# schematic.net
KiCad netlist of a schematic drawn in Altium Designer
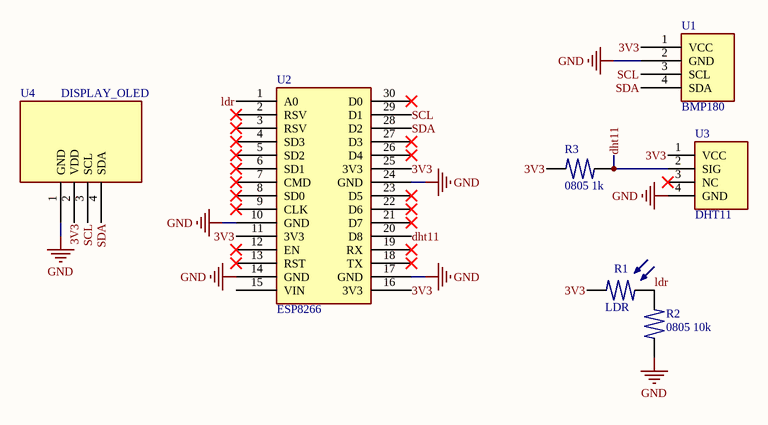
[diagram p0: schematic.SchDoc]

(export (version "E")
  (design (tool "Eeschema 10.0.6"))
  (components
    (comp (ref "R1")
      (value "LDR")
      (footprint "LDR")
      (description "LIGHT DEPENDEND RESISTOR/PHOTORESITOR")
      (libsource (lib "Sensors") (part "LDR"))
    )
    (comp (ref "R2")
      (value "0805 10k")
      (footprint "RESISTOR_0805")
      (libsource (lib "Resistors") (part "RESISTOR_0805"))
    )
    (comp (ref "R3")
      (value "0805 1k")
      (footprint "RESISTOR_0805")
      (libsource (lib "Resistors") (part "RESISTOR_0805"))
    )
    (comp (ref "U1")
      (value "BMP180")
      (footprint "BMP180")
      (description "SENSOR ATMOSPHERIC PRESSURE/TEMPERATURE")
      (libsource (lib "Sensors") (part "BMP180"))
    )
    (comp (ref "U2")
      (value "ESP8266")
      (footprint "ESP8266")
      (description "Microcontoller Board 30 Pins Wifi 2.4GHz BLE 4.2 ESP-12F")
      (libsource (lib "Espressif Microcontrollers") (part "ESP8266"))
    )
    (comp (ref "U3")
      (value "DHT11")
      (footprint "DHT11")
      (description "SENSOR HUMIDITY/TEMPERATURE")
      (libsource (lib "Sensors") (part "DHT11"))
    )
    (comp (ref "U4")
      (value "DISPLAY_OLED")
      (footprint "DISPLAY_OLED")
      (libsource (lib "Displays") (part "DISPLAY_OLED"))
    )
  )
  (nets
    (net (code "1") (name "/3V3") (class "Default")
      (node (ref "R1") (pin "1") (pinfunction "1_1") (pintype "passive"))
      (node (ref "R3") (pin "1") (pinfunction "1_1") (pintype "passive"))
      (node (ref "U1") (pin "1") (pinfunction "VCC_1") (pintype "passive"))
      (node (ref "U2") (pin "11") (pinfunction "3V3_11") (pintype "passive"))
      (node (ref "U2") (pin "16") (pinfunction "3V3_16") (pintype "passive"))
      (node (ref "U2") (pin "25") (pinfunction "3V3_25") (pintype "passive"))
      (node (ref "U3") (pin "1") (pinfunction "VCC_1") (pintype "passive"))
      (node (ref "U4") (pin "2") (pinfunction "VDD_2") (pintype "tri_state"))
    )
    (net (code "2") (name "/SCL") (class "Default")
      (node (ref "U1") (pin "3") (pinfunction "SCL_3") (pintype "passive"))
      (node (ref "U2") (pin "29") (pinfunction "D1_29") (pintype "passive"))
      (node (ref "U4") (pin "3") (pinfunction "SCL_3") (pintype "tri_state"))
    )
    (net (code "3") (name "/SDA") (class "Default")
      (node (ref "U1") (pin "4") (pinfunction "SDA_4") (pintype "passive"))
      (node (ref "U2") (pin "28") (pinfunction "D2_28") (pintype "passive"))
      (node (ref "U4") (pin "4") (pinfunction "SDA_4") (pintype "tri_state"))
    )
    (net (code "4") (name "/dht11") (class "Default")
      (node (ref "R3") (pin "2") (pinfunction "2_2") (pintype "passive"))
      (node (ref "U2") (pin "20") (pinfunction "D8_20") (pintype "passive"))
      (node (ref "U3") (pin "2") (pinfunction "SIG_2") (pintype "passive"))
    )
    (net (code "5") (name "/ldr") (class "Default")
      (node (ref "R1") (pin "2") (pinfunction "2_2") (pintype "passive"))
      (node (ref "R2") (pin "2") (pinfunction "2_2") (pintype "passive"))
      (node (ref "U2") (pin "1") (pinfunction "A0_1") (pintype "passive"))
    )
    (net (code "6") (name "GND") (class "Default")
      (node (ref "R2") (pin "1") (pinfunction "1_1") (pintype "passive"))
      (node (ref "U1") (pin "2") (pinfunction "GND_2") (pintype "passive"))
      (node (ref "U2") (pin "10") (pinfunction "GND_10") (pintype "passive"))
      (node (ref "U2") (pin "14") (pinfunction "GND_14") (pintype "passive"))
      (node (ref "U2") (pin "17") (pinfunction "GND_17") (pintype "passive"))
      (node (ref "U2") (pin "24") (pinfunction "GND_24") (pintype "passive"))
      (node (ref "U3") (pin "4") (pinfunction "GND_4") (pintype "passive"))
      (node (ref "U4") (pin "1") (pinfunction "GND_1") (pintype "tri_state"))
    )
    (net (code "7") (name "unconnected-(U2-CLK-Pad9)") (class "Default")
      (node (ref "U2") (pin "9") (pinfunction "CLK_9") (pintype "passive+no_connect"))
    )
    (net (code "8") (name "unconnected-(U2-CMD-Pad7)") (class "Default")
      (node (ref "U2") (pin "7") (pinfunction "CMD_7") (pintype "passive+no_connect"))
    )
    (net (code "9") (name "unconnected-(U2-D0-Pad30)") (class "Default")
      (node (ref "U2") (pin "30") (pinfunction "D0_30") (pintype "passive+no_connect"))
    )
    (net (code "10") (name "unconnected-(U2-D3-Pad27)") (class "Default")
      (node (ref "U2") (pin "27") (pinfunction "D3_27") (pintype "passive+no_connect"))
    )
    (net (code "11") (name "unconnected-(U2-D4-Pad26)") (class "Default")
      (node (ref "U2") (pin "26") (pinfunction "D4_26") (pintype "passive+no_connect"))
    )
    (net (code "12") (name "unconnected-(U2-D5-Pad23)") (class "Default")
      (node (ref "U2") (pin "23") (pinfunction "D5_23") (pintype "passive+no_connect"))
    )
    (net (code "13") (name "unconnected-(U2-D6-Pad22)") (class "Default")
      (node (ref "U2") (pin "22") (pinfunction "D6_22") (pintype "passive+no_connect"))
    )
    (net (code "14") (name "unconnected-(U2-D7-Pad21)") (class "Default")
      (node (ref "U2") (pin "21") (pinfunction "D7_21") (pintype "passive+no_connect"))
    )
    (net (code "15") (name "unconnected-(U2-EN-Pad12)") (class "Default")
      (node (ref "U2") (pin "12") (pinfunction "EN_12") (pintype "passive+no_connect"))
    )
    (net (code "16") (name "unconnected-(U2-RST-Pad13)") (class "Default")
      (node (ref "U2") (pin "13") (pinfunction "RST_13") (pintype "passive+no_connect"))
    )
    (net (code "17") (name "unconnected-(U2-RSV-Pad2)") (class "Default")
      (node (ref "U2") (pin "2") (pinfunction "RSV_2") (pintype "passive+no_connect"))
    )
    (net (code "18") (name "unconnected-(U2-RSV-Pad3)") (class "Default")
      (node (ref "U2") (pin "3") (pinfunction "RSV_3") (pintype "passive+no_connect"))
    )
    (net (code "19") (name "unconnected-(U2-RX-Pad19)") (class "Default")
      (node (ref "U2") (pin "19") (pinfunction "RX_19") (pintype "passive+no_connect"))
    )
    (net (code "20") (name "unconnected-(U2-SD0-Pad8)") (class "Default")
      (node (ref "U2") (pin "8") (pinfunction "SD0_8") (pintype "passive+no_connect"))
    )
    (net (code "21") (name "unconnected-(U2-SD1-Pad6)") (class "Default")
      (node (ref "U2") (pin "6") (pinfunction "SD1_6") (pintype "passive+no_connect"))
    )
    (net (code "22") (name "unconnected-(U2-SD2-Pad5)") (class "Default")
      (node (ref "U2") (pin "5") (pinfunction "SD2_5") (pintype "passive+no_connect"))
    )
    (net (code "23") (name "unconnected-(U2-SD3-Pad4)") (class "Default")
      (node (ref "U2") (pin "4") (pinfunction "SD3_4") (pintype "passive+no_connect"))
    )
    (net (code "24") (name "unconnected-(U2-TX-Pad18)") (class "Default")
      (node (ref "U2") (pin "18") (pinfunction "TX_18") (pintype "passive+no_connect"))
    )
    (net (code "25") (name "unconnected-(U2-VIN-Pad15)") (class "Default")
      (node (ref "U2") (pin "15") (pinfunction "VIN_15") (pintype "passive"))
    )
    (net (code "26") (name "unconnected-(U3-NC-Pad3)") (class "Default")
      (node (ref "U3") (pin "3") (pinfunction "NC_3") (pintype "passive+no_connect"))
    )
  )
)
